# ZynqPS_DDR.net
KiCad netlist of a schematic drawn in Altium Designer
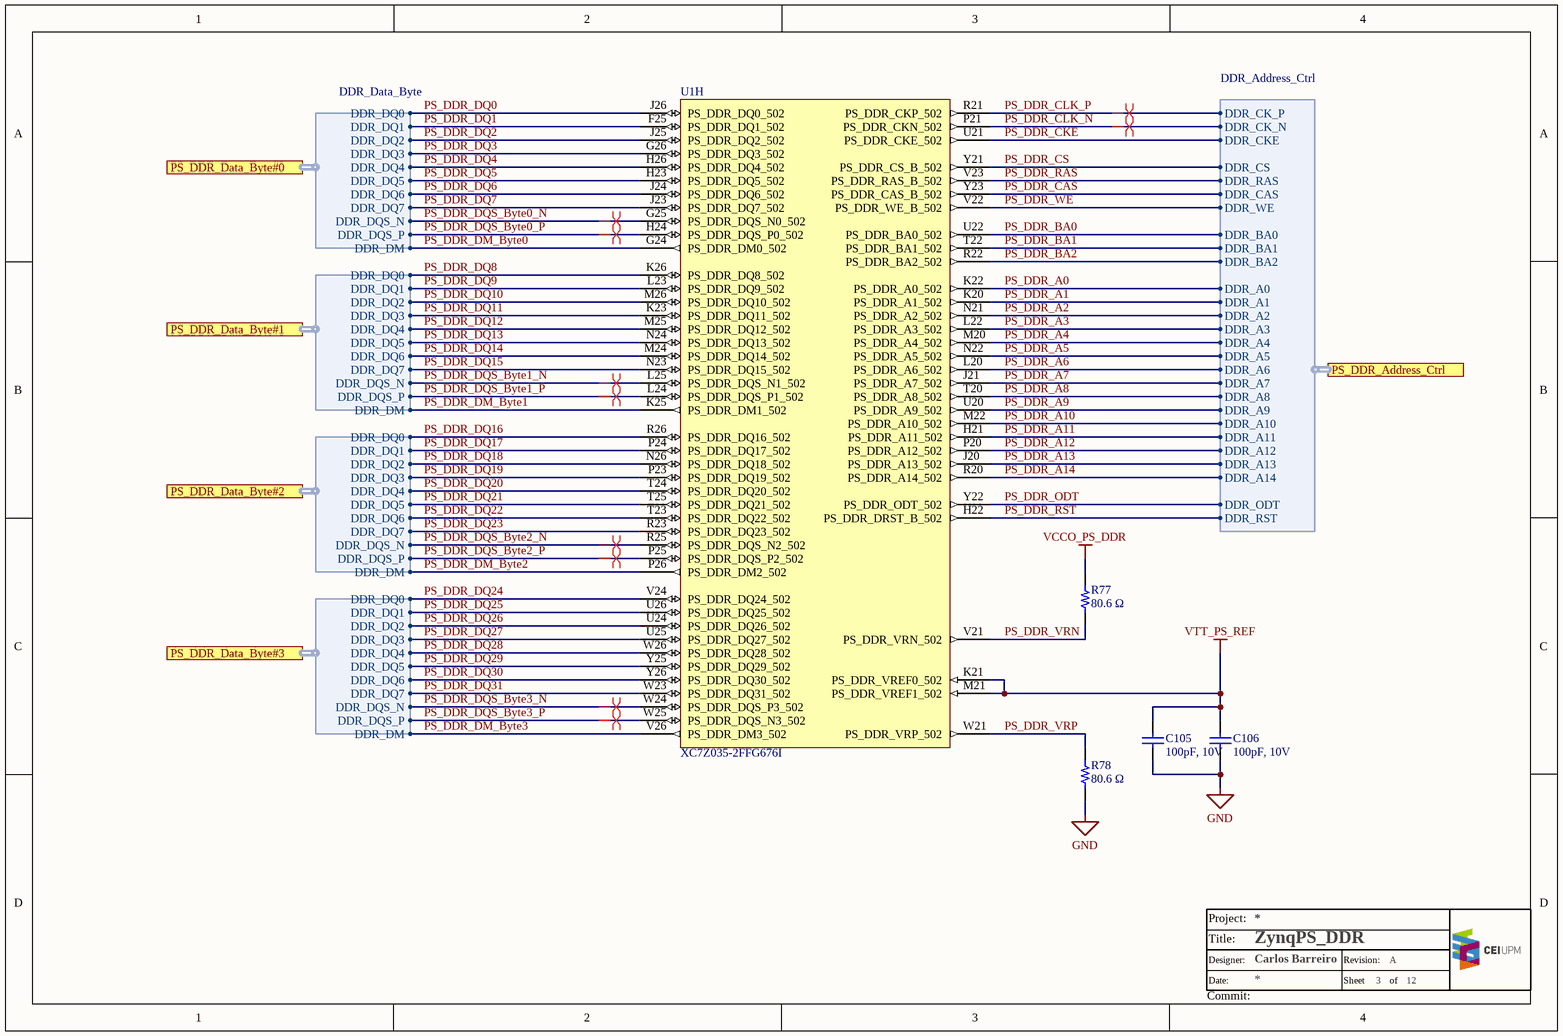
[diagram p0: ZynqPS_DDR.SchDoc]

(export (version "E")
  (design (tool "Eeschema 10.0.6"))
  (components
    (comp (ref "C105")
      (value "100pF, 10V")
      (footprint "WURTH_WCAP-CSGP_0402")
      (description "WCAP-CSGP Multilayer Ceramic Chip Capacitor, General Purpose, size 0402, NP0, 100pF, 10V")
      (fields
        (field (name "MANUFACTURER PART NUMBER") "885012005013")
        (field (name "MANUFACTURER") "Wurth Elektronik")
      )
      (libsource (lib "SpaceVNX") (part "885012005013"))
    )
    (comp (ref "C106")
      (value "100pF, 10V")
      (footprint "WURTH_WCAP-CSGP_0402")
      (description "WCAP-CSGP Multilayer Ceramic Chip Capacitor, General Purpose, size 0402, NP0, 100pF, 10V")
      (fields
        (field (name "MANUFACTURER PART NUMBER") "885012005013")
        (field (name "MANUFACTURER") "Wurth Elektronik")
      )
      (libsource (lib "SpaceVNX") (part "885012005013"))
    )
    (comp (ref "R77")
      (value "80.6 Ω")
      (footprint "PANASONIC_ERJ2G_0402")
      (description "General Purpose Thick Film Chip Resistors")
      (fields (field (name "MANUFACTURER") "Panasonic"))
      (libsource (lib "SpaceVNX") (part "ERJ2RKF80R6X"))
    )
    (comp (ref "R78")
      (value "80.6 Ω")
      (footprint "PANASONIC_ERJ2G_0402")
      (description "General Purpose Thick Film Chip Resistors")
      (fields (field (name "MANUFACTURER") "Panasonic"))
      (libsource (lib "SpaceVNX") (part "ERJ2RKF80R6X"))
    )
    (comp (ref "U1")
      (value "XC7Z035-2FFG676I")
      (footprint "XILINX_FBG676")
      (fields (field (name "PARTNUMBER") "XC7Z035-2FBG676I") (field (name "GENERIC PART NUMBER") "XC7Z035"))
      (libsource (lib "SpaceVNX") (part "XC7Z035-2FFG676I"))
    )
  )
  (nets
    (net (code "3") (name "/PS_DDR_A0") (class "Default")
      (node (ref "U1") (pin "K22") (pinfunction "PS_DDR_A0_502_K22") (pintype "output"))
    )
    (net (code "4") (name "/PS_DDR_A1") (class "Default")
      (node (ref "U1") (pin "K20") (pinfunction "PS_DDR_A1_502_K20") (pintype "output"))
    )
    (net (code "5") (name "/PS_DDR_A2") (class "Default")
      (node (ref "U1") (pin "N21") (pinfunction "PS_DDR_A2_502_N21") (pintype "output"))
    )
    (net (code "6") (name "/PS_DDR_A3") (class "Default")
      (node (ref "U1") (pin "L22") (pinfunction "PS_DDR_A3_502_L22") (pintype "output"))
    )
    (net (code "7") (name "/PS_DDR_A4") (class "Default")
      (node (ref "U1") (pin "M20") (pinfunction "PS_DDR_A4_502_M20") (pintype "output"))
    )
    (net (code "8") (name "/PS_DDR_A5") (class "Default")
      (node (ref "U1") (pin "N22") (pinfunction "PS_DDR_A5_502_N22") (pintype "output"))
    )
    (net (code "9") (name "/PS_DDR_A6") (class "Default")
      (node (ref "U1") (pin "L20") (pinfunction "PS_DDR_A6_502_L20") (pintype "output"))
    )
    (net (code "10") (name "/PS_DDR_A7") (class "Default")
      (node (ref "U1") (pin "J21") (pinfunction "PS_DDR_A7_502_J21") (pintype "output"))
    )
    (net (code "11") (name "/PS_DDR_A8") (class "Default")
      (node (ref "U1") (pin "T20") (pinfunction "PS_DDR_A8_502_T20") (pintype "output"))
    )
    (net (code "12") (name "/PS_DDR_A9") (class "Default")
      (node (ref "U1") (pin "U20") (pinfunction "PS_DDR_A9_502_U20") (pintype "output"))
    )
    (net (code "13") (name "/PS_DDR_A10") (class "Default")
      (node (ref "U1") (pin "M22") (pinfunction "PS_DDR_A10_502_M22") (pintype "output"))
    )
    (net (code "14") (name "/PS_DDR_A11") (class "Default")
      (node (ref "U1") (pin "H21") (pinfunction "PS_DDR_A11_502_H21") (pintype "output"))
    )
    (net (code "15") (name "/PS_DDR_A12") (class "Default")
      (node (ref "U1") (pin "P20") (pinfunction "PS_DDR_A12_502_P20") (pintype "output"))
    )
    (net (code "16") (name "/PS_DDR_A13") (class "Default")
      (node (ref "U1") (pin "J20") (pinfunction "PS_DDR_A13_502_J20") (pintype "output"))
    )
    (net (code "17") (name "/PS_DDR_A14") (class "Default")
      (node (ref "U1") (pin "R20") (pinfunction "PS_DDR_A14_502_R20") (pintype "output"))
    )
    (net (code "18") (name "/PS_DDR_BA0") (class "Default")
      (node (ref "U1") (pin "U22") (pinfunction "PS_DDR_BA0_502_U22") (pintype "output"))
    )
    (net (code "19") (name "/PS_DDR_BA1") (class "Default")
      (node (ref "U1") (pin "T22") (pinfunction "PS_DDR_BA1_502_T22") (pintype "output"))
    )
    (net (code "20") (name "/PS_DDR_BA2") (class "Default")
      (node (ref "U1") (pin "R22") (pinfunction "PS_DDR_BA2_502_R22") (pintype "output"))
    )
    (net (code "21") (name "/PS_DDR_CAS") (class "Default")
      (node (ref "U1") (pin "Y23") (pinfunction "PS_DDR_CAS_B_502_Y23") (pintype "output"))
    )
    (net (code "22") (name "/PS_DDR_CKE") (class "Default")
      (node (ref "U1") (pin "U21") (pinfunction "PS_DDR_CKE_502_U21") (pintype "output"))
    )
    (net (code "23") (name "/PS_DDR_CLK_N") (class "Default")
      (node (ref "U1") (pin "P21") (pinfunction "PS_DDR_CKN_502_P21") (pintype "output"))
    )
    (net (code "24") (name "/PS_DDR_CLK_P") (class "Default")
      (node (ref "U1") (pin "R21") (pinfunction "PS_DDR_CKP_502_R21") (pintype "output"))
    )
    (net (code "25") (name "/PS_DDR_CS") (class "Default")
      (node (ref "U1") (pin "Y21") (pinfunction "PS_DDR_CS_B_502_Y21") (pintype "output"))
    )
    (net (code "26") (name "/PS_DDR_DM_Byte0") (class "Default")
      (node (ref "U1") (pin "G24") (pinfunction "PS_DDR_DM0_502_G24") (pintype "output"))
    )
    (net (code "27") (name "/PS_DDR_DM_Byte1") (class "Default")
      (node (ref "U1") (pin "K25") (pinfunction "PS_DDR_DM1_502_K25") (pintype "output"))
    )
    (net (code "28") (name "/PS_DDR_DM_Byte2") (class "Default")
      (node (ref "U1") (pin "P26") (pinfunction "PS_DDR_DM2_502_P26") (pintype "output"))
    )
    (net (code "29") (name "/PS_DDR_DM_Byte3") (class "Default")
      (node (ref "U1") (pin "V26") (pinfunction "PS_DDR_DM3_502_V26") (pintype "output"))
    )
    (net (code "30") (name "/PS_DDR_DQ0") (class "Default")
      (node (ref "U1") (pin "J26") (pinfunction "PS_DDR_DQ0_502_J26") (pintype "bidirectional"))
    )
    (net (code "31") (name "/PS_DDR_DQ1") (class "Default")
      (node (ref "U1") (pin "F25") (pinfunction "PS_DDR_DQ1_502_F25") (pintype "bidirectional"))
    )
    (net (code "32") (name "/PS_DDR_DQ2") (class "Default")
      (node (ref "U1") (pin "J25") (pinfunction "PS_DDR_DQ2_502_J25") (pintype "bidirectional"))
    )
    (net (code "33") (name "/PS_DDR_DQ3") (class "Default")
      (node (ref "U1") (pin "G26") (pinfunction "PS_DDR_DQ3_502_G26") (pintype "bidirectional"))
    )
    (net (code "34") (name "/PS_DDR_DQ4") (class "Default")
      (node (ref "U1") (pin "H26") (pinfunction "PS_DDR_DQ4_502_H26") (pintype "bidirectional"))
    )
    (net (code "35") (name "/PS_DDR_DQ5") (class "Default")
      (node (ref "U1") (pin "H23") (pinfunction "PS_DDR_DQ5_502_H23") (pintype "bidirectional"))
    )
    (net (code "36") (name "/PS_DDR_DQ6") (class "Default")
      (node (ref "U1") (pin "J24") (pinfunction "PS_DDR_DQ6_502_J24") (pintype "bidirectional"))
    )
    (net (code "37") (name "/PS_DDR_DQ7") (class "Default")
      (node (ref "U1") (pin "J23") (pinfunction "PS_DDR_DQ7_502_J23") (pintype "bidirectional"))
    )
    (net (code "38") (name "/PS_DDR_DQ8") (class "Default")
      (node (ref "U1") (pin "K26") (pinfunction "PS_DDR_DQ8_502_K26") (pintype "bidirectional"))
    )
    (net (code "39") (name "/PS_DDR_DQ9") (class "Default")
      (node (ref "U1") (pin "L23") (pinfunction "PS_DDR_DQ9_502_L23") (pintype "bidirectional"))
    )
    (net (code "40") (name "/PS_DDR_DQ10") (class "Default")
      (node (ref "U1") (pin "M26") (pinfunction "PS_DDR_DQ10_502_M26") (pintype "bidirectional"))
    )
    (net (code "41") (name "/PS_DDR_DQ11") (class "Default")
      (node (ref "U1") (pin "K23") (pinfunction "PS_DDR_DQ11_502_K23") (pintype "bidirectional"))
    )
    (net (code "42") (name "/PS_DDR_DQ12") (class "Default")
      (node (ref "U1") (pin "M25") (pinfunction "PS_DDR_DQ12_502_M25") (pintype "bidirectional"))
    )
    (net (code "43") (name "/PS_DDR_DQ13") (class "Default")
      (node (ref "U1") (pin "N24") (pinfunction "PS_DDR_DQ13_502_N24") (pintype "bidirectional"))
    )
    (net (code "44") (name "/PS_DDR_DQ14") (class "Default")
      (node (ref "U1") (pin "M24") (pinfunction "PS_DDR_DQ14_502_M24") (pintype "bidirectional"))
    )
    (net (code "45") (name "/PS_DDR_DQ15") (class "Default")
      (node (ref "U1") (pin "N23") (pinfunction "PS_DDR_DQ15_502_N23") (pintype "bidirectional"))
    )
    (net (code "46") (name "/PS_DDR_DQ16") (class "Default")
      (node (ref "U1") (pin "R26") (pinfunction "PS_DDR_DQ16_502_R26") (pintype "bidirectional"))
    )
    (net (code "47") (name "/PS_DDR_DQ17") (class "Default")
      (node (ref "U1") (pin "P24") (pinfunction "PS_DDR_DQ17_502_P24") (pintype "bidirectional"))
    )
    (net (code "48") (name "/PS_DDR_DQ18") (class "Default")
      (node (ref "U1") (pin "N26") (pinfunction "PS_DDR_DQ18_502_N26") (pintype "bidirectional"))
    )
    (net (code "49") (name "/PS_DDR_DQ19") (class "Default")
      (node (ref "U1") (pin "P23") (pinfunction "PS_DDR_DQ19_502_P23") (pintype "bidirectional"))
    )
    (net (code "50") (name "/PS_DDR_DQ20") (class "Default")
      (node (ref "U1") (pin "T24") (pinfunction "PS_DDR_DQ20_502_T24") (pintype "bidirectional"))
    )
    (net (code "51") (name "/PS_DDR_DQ21") (class "Default")
      (node (ref "U1") (pin "T25") (pinfunction "PS_DDR_DQ21_502_T25") (pintype "bidirectional"))
    )
    (net (code "52") (name "/PS_DDR_DQ22") (class "Default")
      (node (ref "U1") (pin "T23") (pinfunction "PS_DDR_DQ22_502_T23") (pintype "bidirectional"))
    )
    (net (code "53") (name "/PS_DDR_DQ23") (class "Default")
      (node (ref "U1") (pin "R23") (pinfunction "PS_DDR_DQ23_502_R23") (pintype "bidirectional"))
    )
    (net (code "54") (name "/PS_DDR_DQ24") (class "Default")
      (node (ref "U1") (pin "V24") (pinfunction "PS_DDR_DQ24_502_V24") (pintype "bidirectional"))
    )
    (net (code "55") (name "/PS_DDR_DQ25") (class "Default")
      (node (ref "U1") (pin "U26") (pinfunction "PS_DDR_DQ25_502_U26") (pintype "bidirectional"))
    )
    (net (code "56") (name "/PS_DDR_DQ26") (class "Default")
      (node (ref "U1") (pin "U24") (pinfunction "PS_DDR_DQ26_502_U24") (pintype "bidirectional"))
    )
    (net (code "57") (name "/PS_DDR_DQ27") (class "Default")
      (node (ref "U1") (pin "U25") (pinfunction "PS_DDR_DQ27_502_U25") (pintype "bidirectional"))
    )
    (net (code "58") (name "/PS_DDR_DQ28") (class "Default")
      (node (ref "U1") (pin "W26") (pinfunction "PS_DDR_DQ28_502_W26") (pintype "bidirectional"))
    )
    (net (code "59") (name "/PS_DDR_DQ29") (class "Default")
      (node (ref "U1") (pin "Y25") (pinfunction "PS_DDR_DQ29_502_Y25") (pintype "bidirectional"))
    )
    (net (code "60") (name "/PS_DDR_DQ30") (class "Default")
      (node (ref "U1") (pin "Y26") (pinfunction "PS_DDR_DQ30_502_Y26") (pintype "bidirectional"))
    )
    (net (code "61") (name "/PS_DDR_DQ31") (class "Default")
      (node (ref "U1") (pin "W23") (pinfunction "PS_DDR_DQ31_502_W23") (pintype "bidirectional"))
    )
    (net (code "62") (name "/PS_DDR_DQS_Byte0_N") (class "Default")
      (node (ref "U1") (pin "G25") (pinfunction "PS_DDR_DQS_N0_502_G25") (pintype "bidirectional"))
    )
    (net (code "63") (name "/PS_DDR_DQS_Byte0_P") (class "Default")
      (node (ref "U1") (pin "H24") (pinfunction "PS_DDR_DQS_P0_502_H24") (pintype "bidirectional"))
    )
    (net (code "64") (name "/PS_DDR_DQS_Byte1_N") (class "Default")
      (node (ref "U1") (pin "L25") (pinfunction "PS_DDR_DQS_N1_502_L25") (pintype "bidirectional"))
    )
    (net (code "65") (name "/PS_DDR_DQS_Byte1_P") (class "Default")
      (node (ref "U1") (pin "L24") (pinfunction "PS_DDR_DQS_P1_502_L24") (pintype "bidirectional"))
    )
    (net (code "66") (name "/PS_DDR_DQS_Byte2_N") (class "Default")
      (node (ref "U1") (pin "R25") (pinfunction "PS_DDR_DQS_N2_502_R25") (pintype "bidirectional"))
    )
    (net (code "67") (name "/PS_DDR_DQS_Byte2_P") (class "Default")
      (node (ref "U1") (pin "P25") (pinfunction "PS_DDR_DQS_P2_502_P25") (pintype "bidirectional"))
    )
    (net (code "68") (name "/PS_DDR_DQS_Byte3_N") (class "Default")
      (node (ref "U1") (pin "W24") (pinfunction "PS_DDR_DQS_P3_502_W24") (pintype "bidirectional"))
    )
    (net (code "69") (name "/PS_DDR_DQS_Byte3_P") (class "Default")
      (node (ref "U1") (pin "W25") (pinfunction "PS_DDR_DQS_N3_502_W25") (pintype "bidirectional"))
    )
    (net (code "70") (name "/PS_DDR_ODT") (class "Default")
      (node (ref "U1") (pin "Y22") (pinfunction "PS_DDR_ODT_502_Y22") (pintype "output"))
    )
    (net (code "71") (name "/PS_DDR_RAS") (class "Default")
      (node (ref "U1") (pin "V23") (pinfunction "PS_DDR_RAS_B_502_V23") (pintype "output"))
    )
    (net (code "72") (name "/PS_DDR_RST") (class "Default")
      (node (ref "U1") (pin "H22") (pinfunction "PS_DDR_DRST_B_502_H22") (pintype "output"))
    )
    (net (code "73") (name "/PS_DDR_VRN") (class "Default")
      (node (ref "R77") (pin "1") (pinfunction "1_1") (pintype "passive"))
      (node (ref "U1") (pin "V21") (pinfunction "PS_DDR_VRN_502_V21") (pintype "output"))
    )
    (net (code "74") (name "/PS_DDR_VRP") (class "Default")
      (node (ref "R78") (pin "1") (pinfunction "1_1") (pintype "passive"))
      (node (ref "U1") (pin "W21") (pinfunction "PS_DDR_VRP_502_W21") (pintype "output"))
    )
    (net (code "75") (name "/PS_DDR_WE") (class "Default")
      (node (ref "U1") (pin "V22") (pinfunction "PS_DDR_WE_B_502_V22") (pintype "output"))
    )
    (net (code "78") (name "GND") (class "Default")
      (node (ref "C105") (pin "1") (pinfunction "1_1") (pintype "passive"))
      (node (ref "C106") (pin "1") (pinfunction "1_1") (pintype "passive"))
      (node (ref "R78") (pin "2") (pinfunction "2_2") (pintype "passive"))
    )
    (net (code "79") (name "VCCO_PS_DDR") (class "Default")
      (node (ref "R77") (pin "2") (pinfunction "2_2") (pintype "passive"))
    )
    (net (code "80") (name "VTT_PS_REF") (class "Default")
      (node (ref "C105") (pin "2") (pinfunction "2_2") (pintype "passive"))
      (node (ref "C106") (pin "2") (pinfunction "2_2") (pintype "passive"))
      (node (ref "U1") (pin "K21") (pinfunction "PS_DDR_VREF0_502_K21") (pintype "input"))
      (node (ref "U1") (pin "M21") (pinfunction "PS_DDR_VREF1_502_M21") (pintype "input"))
    )
  )
)
